# Papra_v0_4.net
KiCad netlist of a schematic drawn in EAGLE
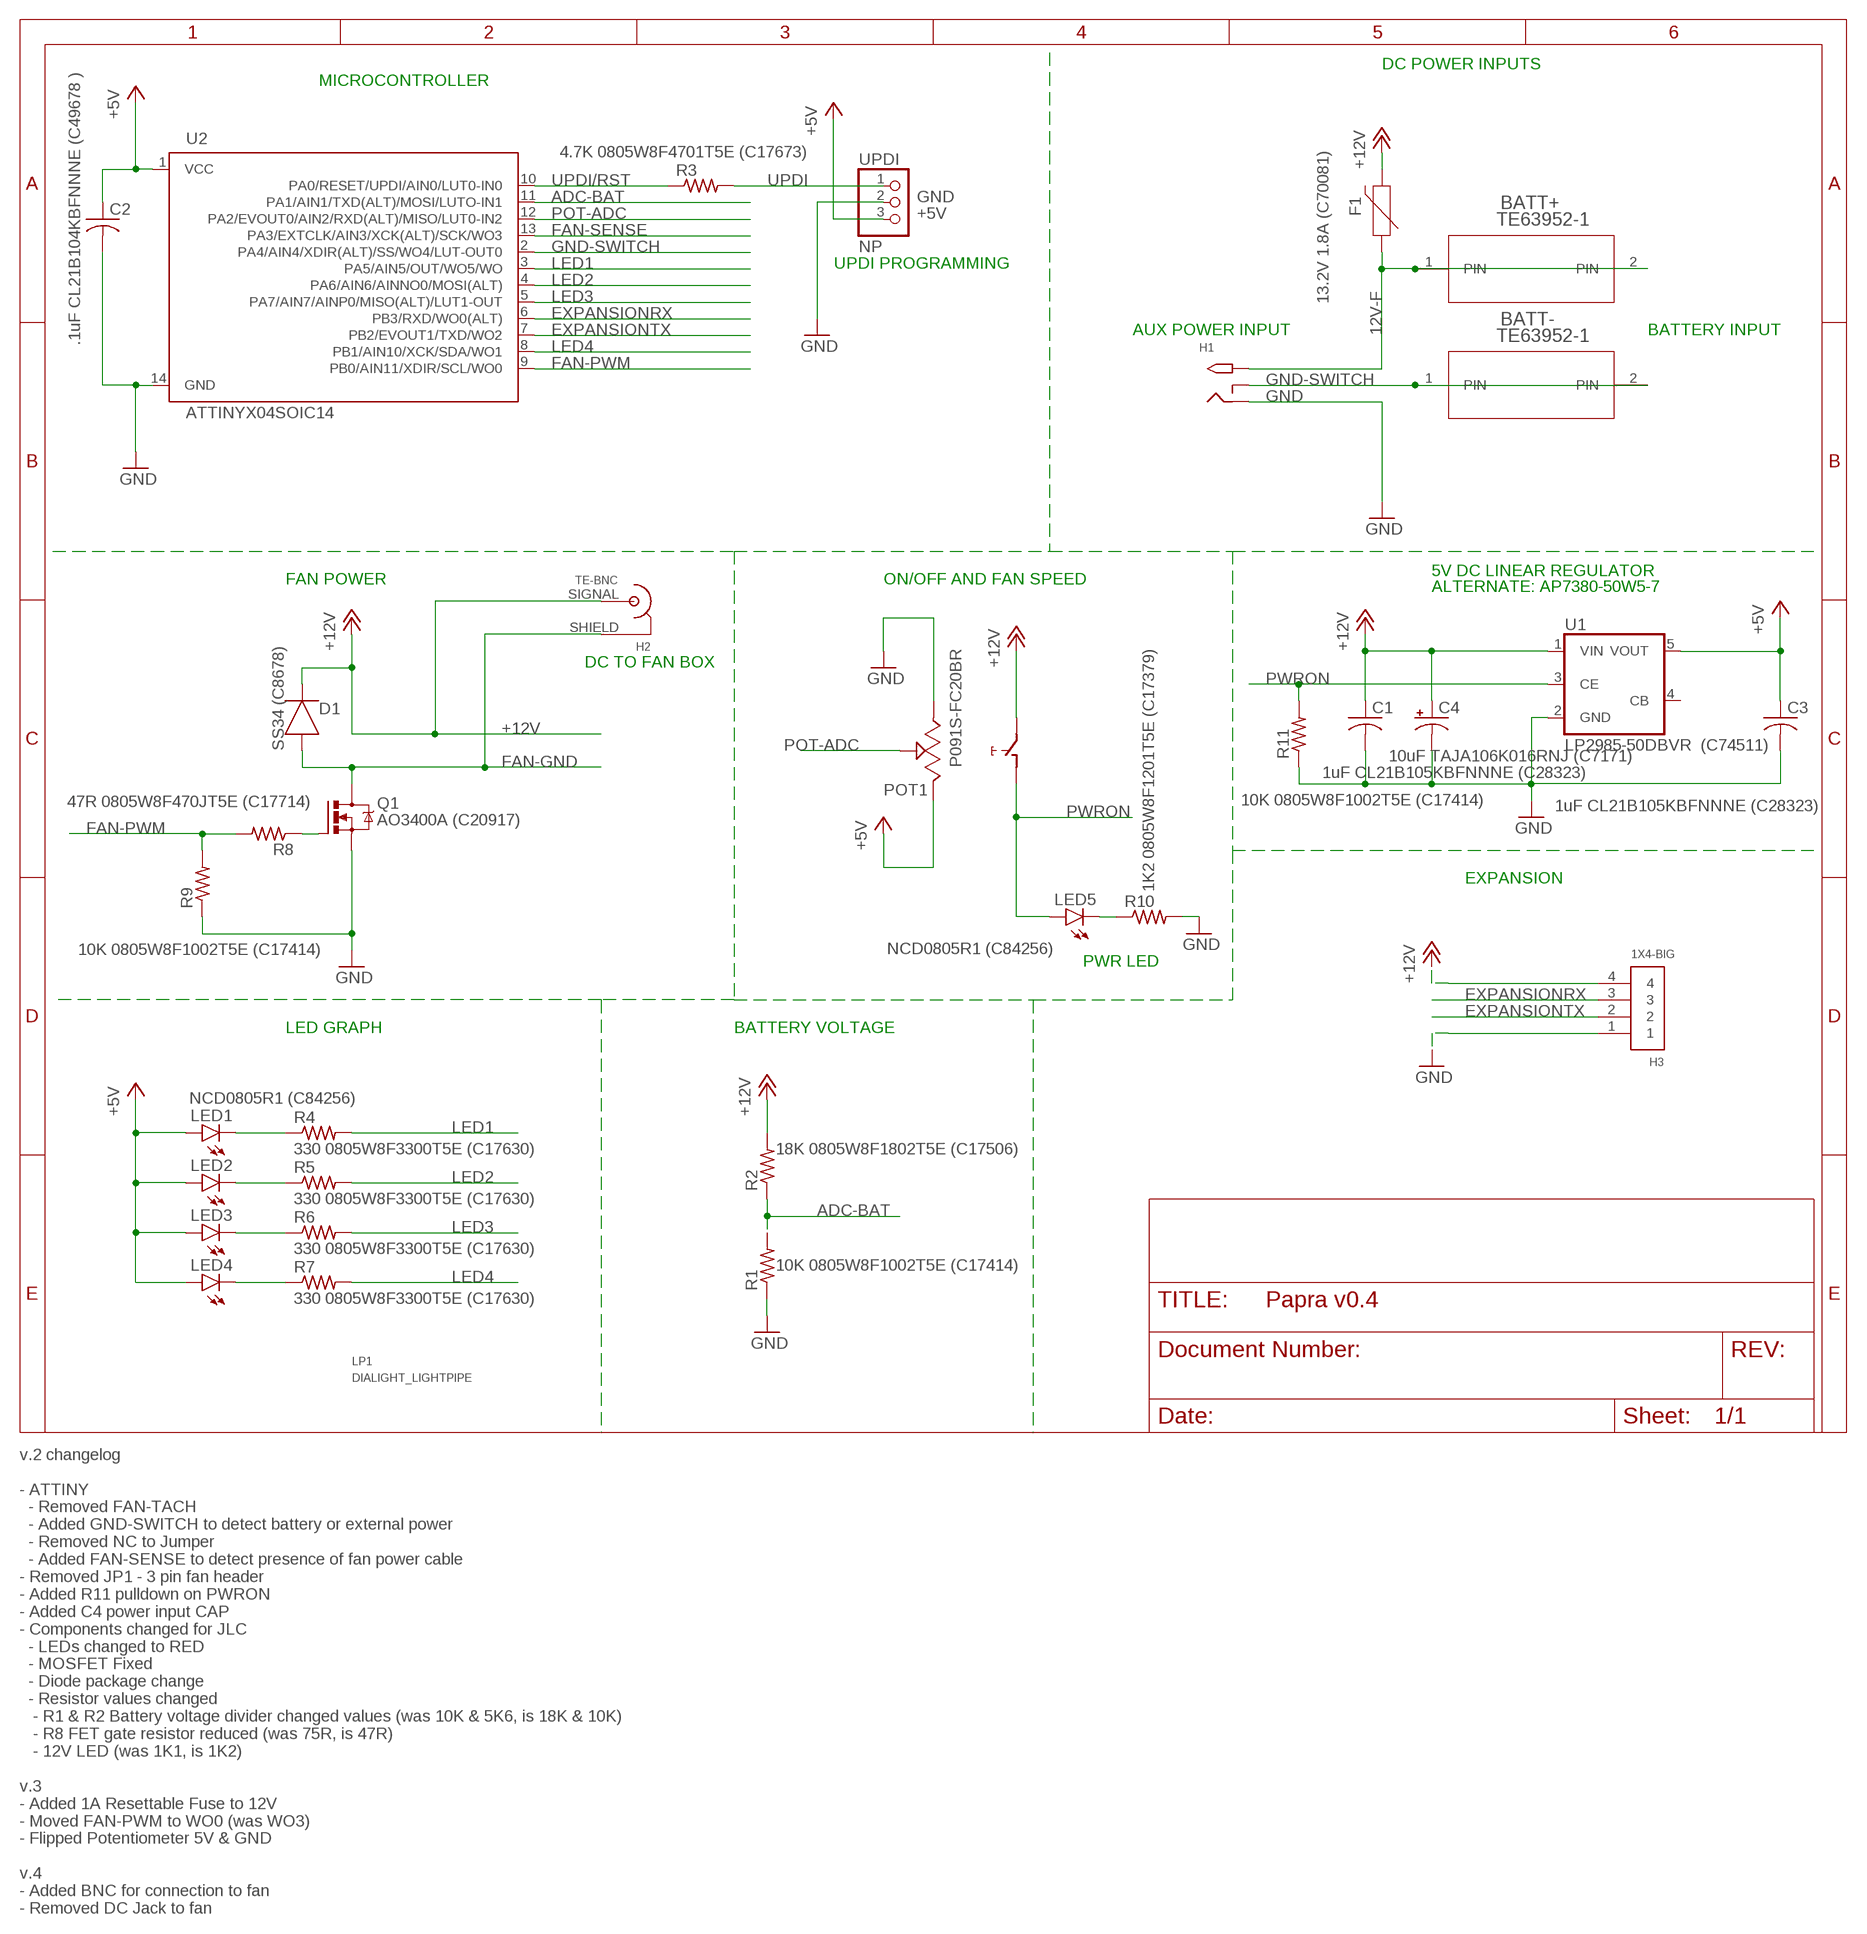
[diagram p0: schematic, sheet 1]

(export (version "E")
  (design (tool "Eeschema 10.0.6"))
  (components
    (comp (ref "BATT+")
      (value "TE63952-1")
      (footprint "eagle-import:TE63952-1")
      (libsource (lib "eagle-import") (part "TE63952-1"))
    )
    (comp (ref "BATT-")
      (value "TE63952-1")
      (footprint "eagle-import:TE63952-1")
      (libsource (lib "eagle-import") (part "TE63952-1"))
    )
    (comp (ref "C1")
      (value "1uF CL21B105KBFNNNE (C28323)")
      (footprint "eagle-import:C0805")
      (libsource (lib "eagle-import") (part "C-USC0805"))
    )
    (comp (ref "C2")
      (value ".1uF CL21B104KBFNNNE (C49678 )")
      (footprint "eagle-import:C0805")
      (libsource (lib "eagle-import") (part "C-USC0805"))
    )
    (comp (ref "C3")
      (value "1uF CL21B105KBFNNNE (C28323)")
      (footprint "eagle-import:C0805")
      (libsource (lib "eagle-import") (part "C-USC0805"))
    )
    (comp (ref "C4")
      (value "10uF TAJA106K016RNJ (C7171)")
      (footprint "eagle-import:A_3216-18R")
      (libsource (lib "eagle-import") (part "CPOL-USA/3216-18R"))
    )
    (comp (ref "D1")
      (value "SS34 (C8678)")
      (footprint "eagle-import:DIOM5226X290N")
      (libsource (lib "eagle-import") (part "DIODEDO-214AC(SMA)"))
    )
    (comp (ref "F1")
      (value "13.2V 1.8A (C70081)")
      (footprint "eagle-import:1206")
      (libsource (lib "eagle-import") (part "PPTC_HALF-AMP"))
    )
    (comp (ref "H1")
      (value "M-CUI-PJ-066A")
      (footprint "eagle-import:DCJACK-PJ-066A")
      (libsource (lib "eagle-import") (part "PJ-066A"))
    )
    (comp (ref "H2")
      (value "TE-BNC")
      (footprint "eagle-import:TE-BNC")
      (libsource (lib "eagle-import") (part "TE-BNC"))
    )
    (comp (ref "H3")
      (value "1X4-BIG")
      (footprint "eagle-import:1X04-BIG")
      (libsource (lib "eagle-import") (part "1X4-BIG"))
    )
    (comp (ref "LED1")
      (value "NCD0805R1 (C84256)")
      (footprint "eagle-import:CHIPLED_0805")
      (libsource (lib "eagle-import") (part "LEDCHIPLED_0805"))
    )
    (comp (ref "LED2")
      (value "NCD0805R1 (C84256)")
      (footprint "eagle-import:CHIPLED_0805")
      (libsource (lib "eagle-import") (part "LEDCHIPLED_0805"))
    )
    (comp (ref "LED3")
      (value "NCD0805R1 (C84256)")
      (footprint "eagle-import:CHIPLED_0805")
      (libsource (lib "eagle-import") (part "LEDCHIPLED_0805"))
    )
    (comp (ref "LED4")
      (value "NCD0805R1 (C84256)")
      (footprint "eagle-import:CHIPLED_0805")
      (libsource (lib "eagle-import") (part "LEDCHIPLED_0805"))
    )
    (comp (ref "LED5")
      (value "NCD0805R1 (C84256)")
      (footprint "eagle-import:CHIPLED_0805")
      (libsource (lib "eagle-import") (part "LEDCHIPLED_0805"))
    )
    (comp (ref "LP1")
      (value "DIALIGHT_LIGHTPIPE")
      (footprint "eagle-import:DIALIGHT_5151020F__LEDS")
      (libsource (lib "eagle-import") (part "DIALIGHT_LIGHTPIPE"))
    )
    (comp (ref "POT1")
      (value "P091S-FC20BR")
      (footprint "eagle-import:P091S-FC20BR")
      (libsource (lib "eagle-import") (part "P091S-FC20BR"))
    )
    (comp (ref "Q1")
      (value "AO3400A (C20917)")
      (footprint "eagle-import:SOT23")
      (fields (field (name "MANUFACTURER") "ON Semiconductor") (field (name "MPN") "BSS123L"))
      (libsource (lib "eagle-import") (part "NMOSFET_-SOT23BSS123"))
    )
    (comp (ref "R1")
      (value "10K 0805W8F1002T5E (C17414)")
      (footprint "eagle-import:R0805")
      (libsource (lib "eagle-import") (part "R-US_R0805"))
    )
    (comp (ref "R2")
      (value "18K 0805W8F1802T5E (C17506)")
      (footprint "eagle-import:R0805")
      (libsource (lib "eagle-import") (part "R-US_R0805"))
    )
    (comp (ref "R3")
      (value "4.7K 0805W8F4701T5E (C17673)")
      (footprint "eagle-import:R0805")
      (libsource (lib "eagle-import") (part "R-US_R0805"))
    )
    (comp (ref "R4")
      (value "330 0805W8F3300T5E (C17630)")
      (footprint "eagle-import:R0805")
      (libsource (lib "eagle-import") (part "R-US_R0805"))
    )
    (comp (ref "R5")
      (value "330 0805W8F3300T5E (C17630)")
      (footprint "eagle-import:R0805")
      (libsource (lib "eagle-import") (part "R-US_R0805"))
    )
    (comp (ref "R6")
      (value "330 0805W8F3300T5E (C17630)")
      (footprint "eagle-import:R0805")
      (libsource (lib "eagle-import") (part "R-US_R0805"))
    )
    (comp (ref "R7")
      (value "330 0805W8F3300T5E (C17630)")
      (footprint "eagle-import:R0805")
      (libsource (lib "eagle-import") (part "R-US_R0805"))
    )
    (comp (ref "R8")
      (value "47R 0805W8F470JT5E (C17714)")
      (footprint "eagle-import:R0805")
      (libsource (lib "eagle-import") (part "R-US_R0805"))
    )
    (comp (ref "R9")
      (value "10K 0805W8F1002T5E (C17414)")
      (footprint "eagle-import:R0805")
      (libsource (lib "eagle-import") (part "R-US_R0805"))
    )
    (comp (ref "R10")
      (value "1K2 0805W8F1201T5E (C17379)")
      (footprint "eagle-import:R0805")
      (libsource (lib "eagle-import") (part "R-US_R0805"))
    )
    (comp (ref "R11")
      (value "10K 0805W8F1002T5E (C17414)")
      (footprint "eagle-import:R0805")
      (libsource (lib "eagle-import") (part "R-US_R0805"))
    )
    (comp (ref "U1")
      (value "LP2985-50DBVR (C74511)")
      (footprint "eagle-import:SOT25")
      (libsource (lib "eagle-import") (part "TS520533"))
    )
    (comp (ref "U2")
      (value "ATTINYX04SOIC14")
      (footprint "eagle-import:SOIC127P600X144-14")
      (libsource (lib "eagle-import") (part "ATTINYX04SOIC14"))
    )
    (comp (ref "UPDI")
      (value "NP")
      (footprint "eagle-import:1X03")
      (libsource (lib "eagle-import") (part "PINHD-1X3"))
    )
  )
  (nets
    (net (code "1") (name "+5V") (class "Default")
      (node (ref "C2") (pin "1") (pinfunction "1_1") (pintype "passive"))
      (node (ref "C3") (pin "1") (pinfunction "1_1") (pintype "passive"))
      (node (ref "LED1") (pin "A") (pinfunction "A_A") (pintype "passive"))
      (node (ref "LED2") (pin "A") (pinfunction "A_A") (pintype "passive"))
      (node (ref "LED3") (pin "A") (pinfunction "A_A") (pintype "passive"))
      (node (ref "LED4") (pin "A") (pinfunction "A_A") (pintype "passive"))
      (node (ref "POT1") (pin "3") (pinfunction "3_3") (pintype "passive"))
      (node (ref "U1") (pin "5") (pinfunction "VOUT_5") (pintype "passive"))
      (node (ref "U2") (pin "1") (pinfunction "VCC_1") (pintype "power_in"))
      (node (ref "UPDI") (pin "3") (pinfunction "3_3") (pintype "passive"))
    )
    (net (code "2") (name "+12V") (class "Default")
      (node (ref "C1") (pin "1") (pinfunction "1_1") (pintype "passive"))
      (node (ref "C4") (pin "+") (pinfunction "+_+") (pintype "passive"))
      (node (ref "D1") (pin "1") (pinfunction "C_1") (pintype "passive"))
      (node (ref "F1") (pin "2") (pinfunction "2_2") (pintype "bidirectional"))
      (node (ref "H2") (pin "SIGNAL") (pinfunction "P1_SIGNAL") (pintype "passive"))
      (node (ref "H3") (pin "4") (pinfunction "4_4") (pintype "bidirectional"))
      (node (ref "POT1") (pin "NO") (pinfunction "5_NO") (pintype "passive"))
      (node (ref "R2") (pin "2") (pinfunction "2_2") (pintype "passive"))
      (node (ref "U1") (pin "1") (pinfunction "VIN_1") (pintype "input"))
    )
    (net (code "3") (name "/12V-F") (class "Default")
      (node (ref "BATT+") (pin "1") (pinfunction "PIN_1") (pintype "passive"))
      (node (ref "BATT+") (pin "2") (pinfunction "PIN_2") (pintype "passive"))
      (node (ref "F1") (pin "1") (pinfunction "1_1") (pintype "bidirectional"))
      (node (ref "H1") (pin "PWR") (pinfunction "TIP_PWR") (pintype "bidirectional"))
    )
    (net (code "4") (name "/ADC-BAT") (class "Default")
      (node (ref "R1") (pin "2") (pinfunction "2_2") (pintype "passive"))
      (node (ref "R2") (pin "1") (pinfunction "1_1") (pintype "passive"))
      (node (ref "U2") (pin "11") (pinfunction "PA1/AIN1/TXD(ALT)/MOSI/LUTO-IN1_11") (pintype "bidirectional"))
    )
    (net (code "5") (name "/EXPANSIONRX") (class "Default")
      (node (ref "H3") (pin "3") (pinfunction "3_3") (pintype "bidirectional"))
      (node (ref "U2") (pin "6") (pinfunction "PB3/RXD/WO0(ALT)_6") (pintype "bidirectional"))
    )
    (net (code "6") (name "/EXPANSIONTX") (class "Default")
      (node (ref "H3") (pin "2") (pinfunction "2_2") (pintype "bidirectional"))
      (node (ref "U2") (pin "7") (pinfunction "PB2/EVOUT1/TXD/WO2_7") (pintype "bidirectional"))
    )
    (net (code "7") (name "/FAN-GND") (class "Default")
      (node (ref "D1") (pin "2") (pinfunction "A_2") (pintype "passive"))
      (node (ref "H2") (pin "SHIELD") (pinfunction "P2_SHIELD") (pintype "passive"))
      (node (ref "Q1") (pin "3") (pinfunction "D_3") (pintype "passive"))
    )
    (net (code "8") (name "/FAN-PWM") (class "Default")
      (node (ref "R8") (pin "2") (pinfunction "2_2") (pintype "passive"))
      (node (ref "R9") (pin "2") (pinfunction "2_2") (pintype "passive"))
      (node (ref "U2") (pin "9") (pinfunction "PB0/AIN11/XDIR/SCL/WO0_9") (pintype "bidirectional"))
    )
    (net (code "9") (name "/FAN-SENSE") (class "Default")
      (node (ref "U2") (pin "13") (pinfunction "PA3/EXTCLK/AIN3/XCK(ALT)/SCK/WO3_13") (pintype "bidirectional"))
    )
    (net (code "10") (name "/GND-SWITCH") (class "Default")
      (node (ref "BATT-") (pin "1") (pinfunction "PIN_1") (pintype "passive"))
      (node (ref "BATT-") (pin "2") (pinfunction "PIN_2") (pintype "passive"))
      (node (ref "H1") (pin "GNDBREAK") (pinfunction "RING_SW_GNDBREAK") (pintype "bidirectional"))
      (node (ref "U2") (pin "2") (pinfunction "PA4/AIN4/XDIR(ALT)/SS/WO4/LUT-OUT0_2") (pintype "bidirectional"))
    )
    (net (code "11") (name "/LED1") (class "Default")
      (node (ref "R4") (pin "2") (pinfunction "2_2") (pintype "passive"))
      (node (ref "U2") (pin "3") (pinfunction "PA5/AIN5/OUT/WO5/WO_3") (pintype "bidirectional"))
    )
    (net (code "12") (name "/LED2") (class "Default")
      (node (ref "R5") (pin "2") (pinfunction "2_2") (pintype "passive"))
      (node (ref "U2") (pin "4") (pinfunction "PA6/AIN6/AINNO0/MOSI(ALT)_4") (pintype "bidirectional"))
    )
    (net (code "13") (name "/LED3") (class "Default")
      (node (ref "R6") (pin "2") (pinfunction "2_2") (pintype "passive"))
      (node (ref "U2") (pin "5") (pinfunction "PA7/AIN7/AINP0/MISO(ALT)/LUT1-OUT_5") (pintype "bidirectional"))
    )
    (net (code "14") (name "/LED4") (class "Default")
      (node (ref "R7") (pin "2") (pinfunction "2_2") (pintype "passive"))
      (node (ref "U2") (pin "8") (pinfunction "PB1/AIN10/XCK/SDA/WO1_8") (pintype "bidirectional"))
    )
    (net (code "15") (name "/POT-ADC") (class "Default")
      (node (ref "POT1") (pin "2") (pinfunction "2_2") (pintype "passive"))
      (node (ref "U2") (pin "12") (pinfunction "PA2/EVOUT0/AIN2/RXD(ALT)/MISO/LUT0-IN2_12") (pintype "bidirectional"))
    )
    (net (code "16") (name "/PWRON") (class "Default")
      (node (ref "LED5") (pin "A") (pinfunction "A_A") (pintype "passive"))
      (node (ref "POT1") (pin "COM") (pinfunction "4_COM") (pintype "passive"))
      (node (ref "R11") (pin "2") (pinfunction "2_2") (pintype "passive"))
      (node (ref "U1") (pin "3") (pinfunction "CE_3") (pintype "input"))
    )
    (net (code "17") (name "/UPDI") (class "Default")
      (node (ref "R3") (pin "2") (pinfunction "2_2") (pintype "passive"))
      (node (ref "UPDI") (pin "1") (pinfunction "1_1") (pintype "passive"))
    )
    (net (code "18") (name "/UPDI{slash}RST") (class "Default")
      (node (ref "R3") (pin "1") (pinfunction "1_1") (pintype "passive"))
      (node (ref "U2") (pin "10") (pinfunction "PA0/RESET/UPDI/AIN0/LUT0-IN0_10") (pintype "bidirectional"))
    )
    (net (code "19") (name "GND") (class "Default")
      (node (ref "C1") (pin "2") (pinfunction "2_2") (pintype "passive"))
      (node (ref "C2") (pin "2") (pinfunction "2_2") (pintype "passive"))
      (node (ref "C3") (pin "2") (pinfunction "2_2") (pintype "passive"))
      (node (ref "C4") (pin "-") (pinfunction "-_-") (pintype "passive"))
      (node (ref "H1") (pin "GND") (pinfunction "RING_GND") (pintype "bidirectional"))
      (node (ref "H3") (pin "1") (pinfunction "1_1") (pintype "bidirectional"))
      (node (ref "POT1") (pin "1") (pinfunction "1_1") (pintype "passive"))
      (node (ref "Q1") (pin "2") (pinfunction "S_2") (pintype "passive"))
      (node (ref "R1") (pin "1") (pinfunction "1_1") (pintype "passive"))
      (node (ref "R10") (pin "2") (pinfunction "2_2") (pintype "passive"))
      (node (ref "R11") (pin "1") (pinfunction "1_1") (pintype "passive"))
      (node (ref "R9") (pin "1") (pinfunction "1_1") (pintype "passive"))
      (node (ref "U1") (pin "2") (pinfunction "GND_2") (pintype "passive"))
      (node (ref "U2") (pin "14") (pinfunction "GND_14") (pintype "power_in"))
      (node (ref "UPDI") (pin "2") (pinfunction "2_2") (pintype "passive"))
    )
    (net (code "20") (name "Net-(LED1-PadC)") (class "Default")
      (node (ref "LED1") (pin "C") (pinfunction "C_C") (pintype "passive"))
      (node (ref "R4") (pin "1") (pinfunction "1_1") (pintype "passive"))
    )
    (net (code "21") (name "Net-(LED2-PadC)") (class "Default")
      (node (ref "LED2") (pin "C") (pinfunction "C_C") (pintype "passive"))
      (node (ref "R5") (pin "1") (pinfunction "1_1") (pintype "passive"))
    )
    (net (code "22") (name "Net-(LED3-PadC)") (class "Default")
      (node (ref "LED3") (pin "C") (pinfunction "C_C") (pintype "passive"))
      (node (ref "R6") (pin "1") (pinfunction "1_1") (pintype "passive"))
    )
    (net (code "23") (name "Net-(LED4-PadC)") (class "Default")
      (node (ref "LED4") (pin "C") (pinfunction "C_C") (pintype "passive"))
      (node (ref "R7") (pin "1") (pinfunction "1_1") (pintype "passive"))
    )
    (net (code "24") (name "Net-(LED5-PadC)") (class "Default")
      (node (ref "LED5") (pin "C") (pinfunction "C_C") (pintype "passive"))
      (node (ref "R10") (pin "1") (pinfunction "1_1") (pintype "passive"))
    )
    (net (code "25") (name "Net-(Q1-G)") (class "Default")
      (node (ref "Q1") (pin "1") (pinfunction "G_1") (pintype "passive"))
      (node (ref "R8") (pin "1") (pinfunction "1_1") (pintype "passive"))
    )
    (net (code "26") (name "unconnected-(U1-CB-Pad4)") (class "Default")
      (node (ref "U1") (pin "4") (pinfunction "CB_4") (pintype "input"))
    )
  )
)
